# Sunflower.net
KiCad netlist of a schematic drawn in Altium Designer
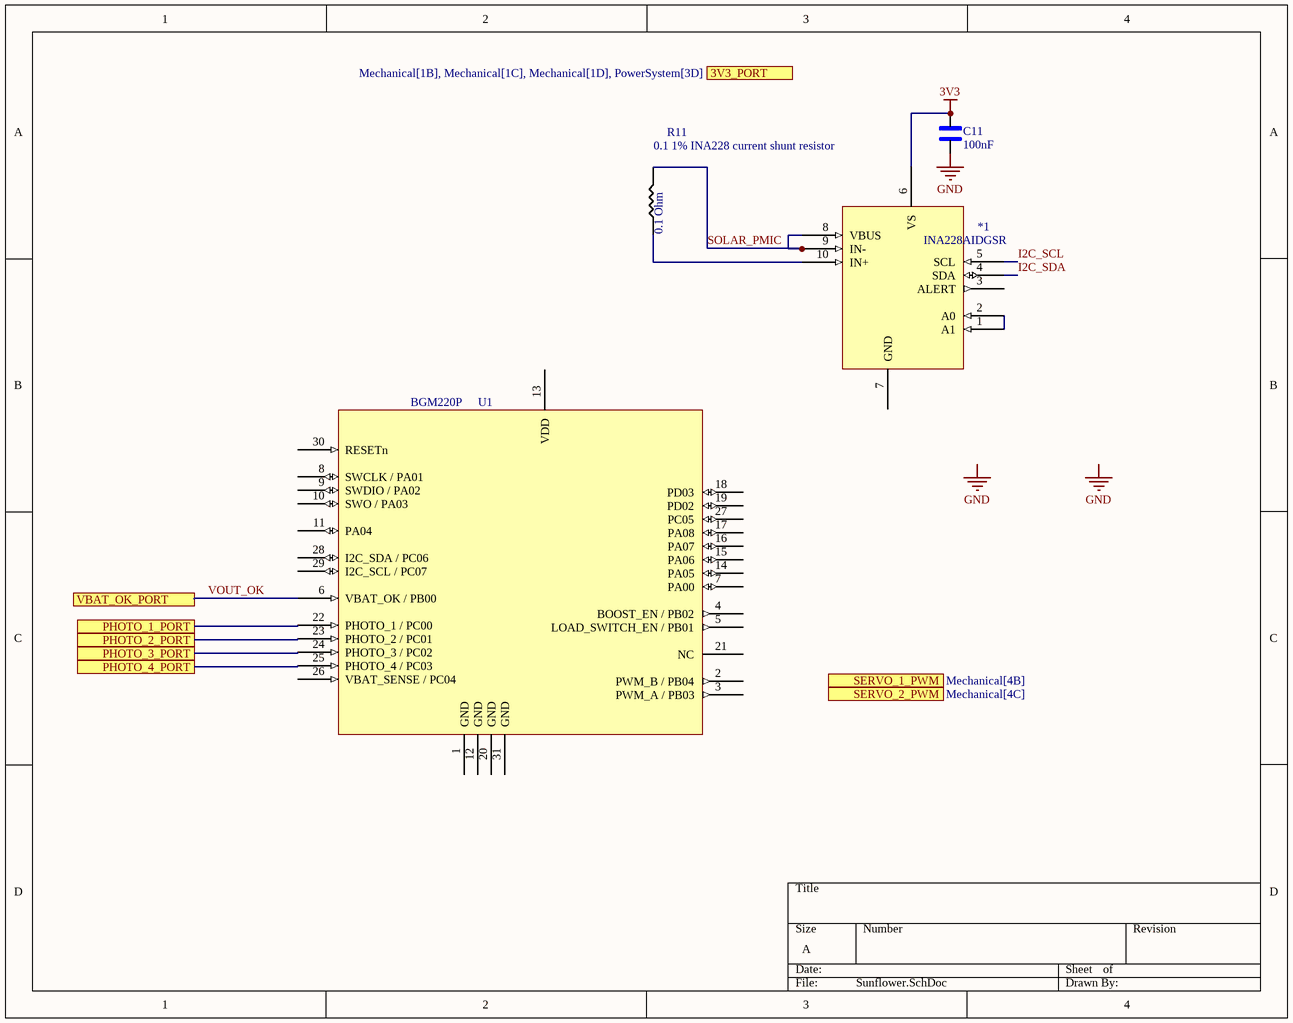
[diagram p0: Sunflower.SchDoc]

(export (version "E")
  (design (tool "Eeschema 10.0.6"))
  (components
    (comp (ref "*1")
      (value "INA228AIDGSR")
      (footprint "DGS0010A")
      (description "General Purpose Amplifiers; INA228AIDGSR; TEXAS INSTRUMENTS; 10; 3 mm; 3 mm; 5.5 V")
      (fields
        (field (name "MANUFACTURER") "Texas Instruments")
        (field (name "DIGIKEY PART NUMBER") "296-INA228AIDGSRCT-ND")
      )
      (libsource (lib "SunflowerSCH") (part "INA228AIDGSR"))
    )
    (comp (ref "C11")
      (value "100nF")
      (footprint "0402_Capacitor")
      (description "0402 ceramic decoupling capacitor, 0.1 µF")
      (fields (field (name "MFR PART #") "CL05A105KA5NQNC") (field (name "LCSC PART#") "C52923"))
      (libsource (lib "SunflowerSCH") (part "C_0402_100nF"))
    )
    (comp (ref "R11")
      (value "0.1 1% INA228 current shunt resistor")
      (footprint "0603_Resistor")
      (description "Res Thick Film 0603 0.1 Ohm 1% 0.25W ±300ppm/°C Molded SMD Punched Carrier T/R")
      (fields
        (field (name "MANUFACTURER") "Panasonic")
        (field (name "MANUFACTURER PART NUMBER") "ERJ3BSFR10V")
      )
      (libsource (lib "SunflowerSCH") (part "ERJ3BSFR10V"))
    )
    (comp (ref "U1")
      (value "BGM220P")
      (footprint "BGM220PC22HNA2")
      (description "Wireless bluetooth PCB module, Secure Boot w/Root of Trust and Secure Loader, Built-in antenna")
      (fields
        (field (name "MANUFACTURER") "Silicon Lab")
        (field (name "MANUFACTURER PART NUMBER") "BGM220PC22HNA2R")
      )
      (libsource (lib "SunflowerSCH") (part "BGM220PC22HNA2R"))
    )
  )
  (nets
    (net (code "2") (name "/I2C_SCL") (class "Default")
      (node (ref "*1") (pin "5") (pinfunction "SCL_5") (pintype "input"))
    )
    (net (code "3") (name "/I2C_SDA") (class "Default")
      (node (ref "*1") (pin "4") (pinfunction "SDA_4") (pintype "bidirectional"))
    )
    (net (code "4") (name "/PHOTO_1_PORT") (class "Default")
      (node (ref "U1") (pin "22") (pinfunction "PHOTO_1_/_PC00_22") (pintype "input"))
    )
    (net (code "5") (name "/PHOTO_2_PORT") (class "Default")
      (node (ref "U1") (pin "23") (pinfunction "PHOTO_2_/_PC01_23") (pintype "input"))
    )
    (net (code "6") (name "/PHOTO_3_PORT") (class "Default")
      (node (ref "U1") (pin "24") (pinfunction "PHOTO_3_/_PC02_24") (pintype "input"))
    )
    (net (code "7") (name "/PHOTO_4_PORT") (class "Default")
      (node (ref "U1") (pin "25") (pinfunction "PHOTO_4_/_PC03_25") (pintype "input"))
    )
    (net (code "10") (name "/SOLAR_PMIC") (class "Default")
      (node (ref "*1") (pin "8") (pinfunction "VBUS_8") (pintype "input"))
      (node (ref "*1") (pin "9") (pinfunction "IN-_9") (pintype "input"))
      (node (ref "R11") (pin "2") (pinfunction "2_2") (pintype "passive"))
    )
    (net (code "11") (name "/VOUT_OK") (class "Default")
      (node (ref "U1") (pin "6") (pinfunction "VBAT_OK_/_PB00_6") (pintype "input"))
    )
    (net (code "12") (name "3V3") (class "Default")
      (node (ref "*1") (pin "6") (pinfunction "VS_6") (pintype "power_in"))
      (node (ref "C11") (pin "1") (pinfunction "1_1") (pintype "passive"))
    )
    (net (code "13") (name "GND") (class "Default")
      (node (ref "C11") (pin "2") (pinfunction "2_2") (pintype "passive"))
    )
    (net (code "14") (name "Net-(*1-A0)") (class "Default")
      (node (ref "*1") (pin "1") (pinfunction "A1_1") (pintype "input"))
      (node (ref "*1") (pin "2") (pinfunction "A0_2") (pintype "input"))
    )
    (net (code "15") (name "Net-(*1-IN+)") (class "Default")
      (node (ref "*1") (pin "10") (pinfunction "IN+_10") (pintype "input"))
      (node (ref "R11") (pin "1") (pinfunction "1_1") (pintype "passive"))
    )
    (net (code "16") (name "unconnected-(*1-ALERT-Pad3)") (class "Default")
      (node (ref "*1") (pin "3") (pinfunction "ALERT_3") (pintype "output"))
    )
    (net (code "17") (name "unconnected-(*1-GND-Pad7)") (class "Default")
      (node (ref "*1") (pin "7") (pinfunction "GND_7") (pintype "power_in"))
    )
    (net (code "18") (name "unconnected-(U1-BOOST_EN_{slash}_PB02-Pad4)") (class "Default")
      (node (ref "U1") (pin "4") (pinfunction "BOOST_EN_/_PB02_4") (pintype "output"))
    )
    (net (code "19") (name "unconnected-(U1-GND-Pad1)") (class "Default")
      (node (ref "U1") (pin "1") (pinfunction "GND_1") (pintype "power_in"))
    )
    (net (code "20") (name "unconnected-(U1-GND-Pad12)") (class "Default")
      (node (ref "U1") (pin "12") (pinfunction "GND_12") (pintype "power_in"))
    )
    (net (code "21") (name "unconnected-(U1-GND-Pad20)") (class "Default")
      (node (ref "U1") (pin "20") (pinfunction "GND_20") (pintype "power_in"))
    )
    (net (code "22") (name "unconnected-(U1-GND-Pad31)") (class "Default")
      (node (ref "U1") (pin "31") (pinfunction "GND_31") (pintype "power_in"))
    )
    (net (code "23") (name "unconnected-(U1-I2C_SCL_{slash}_PC07-Pad29)") (class "Default")
      (node (ref "U1") (pin "29") (pinfunction "I2C_SCL_/_PC07_29") (pintype "bidirectional"))
    )
    (net (code "24") (name "unconnected-(U1-I2C_SDA_{slash}_PC06-Pad28)") (class "Default")
      (node (ref "U1") (pin "28") (pinfunction "I2C_SDA_/_PC06_28") (pintype "bidirectional"))
    )
    (net (code "25") (name "unconnected-(U1-LOAD_SWITCH_EN_{slash}_PB01-Pad5)") (class "Default")
      (node (ref "U1") (pin "5") (pinfunction "LOAD_SWITCH_EN_/_PB01_5") (pintype "output"))
    )
    (net (code "26") (name "unconnected-(U1-NC-Pad21)") (class "Default")
      (node (ref "U1") (pin "21") (pinfunction "NC_21") (pintype "passive"))
    )
    (net (code "27") (name "unconnected-(U1-PA00-Pad7)") (class "Default")
      (node (ref "U1") (pin "7") (pinfunction "PA00_7") (pintype "bidirectional"))
    )
    (net (code "28") (name "unconnected-(U1-PA04-Pad11)") (class "Default")
      (node (ref "U1") (pin "11") (pinfunction "PA04_11") (pintype "bidirectional"))
    )
    (net (code "29") (name "unconnected-(U1-PA05-Pad14)") (class "Default")
      (node (ref "U1") (pin "14") (pinfunction "PA05_14") (pintype "bidirectional"))
    )
    (net (code "30") (name "unconnected-(U1-PA06-Pad15)") (class "Default")
      (node (ref "U1") (pin "15") (pinfunction "PA06_15") (pintype "bidirectional"))
    )
    (net (code "31") (name "unconnected-(U1-PA07-Pad16)") (class "Default")
      (node (ref "U1") (pin "16") (pinfunction "PA07_16") (pintype "bidirectional"))
    )
    (net (code "32") (name "unconnected-(U1-PA08-Pad17)") (class "Default")
      (node (ref "U1") (pin "17") (pinfunction "PA08_17") (pintype "bidirectional"))
    )
    (net (code "33") (name "unconnected-(U1-PC05-Pad27)") (class "Default")
      (node (ref "U1") (pin "27") (pinfunction "PC05_27") (pintype "bidirectional"))
    )
    (net (code "34") (name "unconnected-(U1-PD02-Pad19)") (class "Default")
      (node (ref "U1") (pin "19") (pinfunction "PD02_19") (pintype "bidirectional"))
    )
    (net (code "35") (name "unconnected-(U1-PD03-Pad18)") (class "Default")
      (node (ref "U1") (pin "18") (pinfunction "PD03_18") (pintype "bidirectional"))
    )
    (net (code "36") (name "unconnected-(U1-PWM_A_{slash}_PB03-Pad3)") (class "Default")
      (node (ref "U1") (pin "3") (pinfunction "PWM_A_/_PB03_3") (pintype "output"))
    )
    (net (code "37") (name "unconnected-(U1-PWM_B_{slash}_PB04-Pad2)") (class "Default")
      (node (ref "U1") (pin "2") (pinfunction "PWM_B_/_PB04_2") (pintype "output"))
    )
    (net (code "38") (name "unconnected-(U1-RESETn-Pad30)") (class "Default")
      (node (ref "U1") (pin "30") (pinfunction "RESETn_30") (pintype "input"))
    )
    (net (code "39") (name "unconnected-(U1-SWCLK_{slash}_PA01-Pad8)") (class "Default")
      (node (ref "U1") (pin "8") (pinfunction "SWCLK_/_PA01_8") (pintype "bidirectional"))
    )
    (net (code "40") (name "unconnected-(U1-SWDIO_{slash}_PA02-Pad9)") (class "Default")
      (node (ref "U1") (pin "9") (pinfunction "SWDIO_/_PA02_9") (pintype "bidirectional"))
    )
    (net (code "41") (name "unconnected-(U1-SWO_{slash}_PA03-Pad10)") (class "Default")
      (node (ref "U1") (pin "10") (pinfunction "SWO_/_PA03_10") (pintype "bidirectional"))
    )
    (net (code "42") (name "unconnected-(U1-VBAT_SENSE_{slash}_PC04-Pad26)") (class "Default")
      (node (ref "U1") (pin "26") (pinfunction "VBAT_SENSE_/_PC04_26") (pintype "input"))
    )
    (net (code "43") (name "unconnected-(U1-VDD-Pad13)") (class "Default")
      (node (ref "U1") (pin "13") (pinfunction "VDD_13") (pintype "power_in"))
    )
  )
)
